# AugmentedStethoscope_v2b.net
KiCad netlist of a schematic drawn in EAGLE
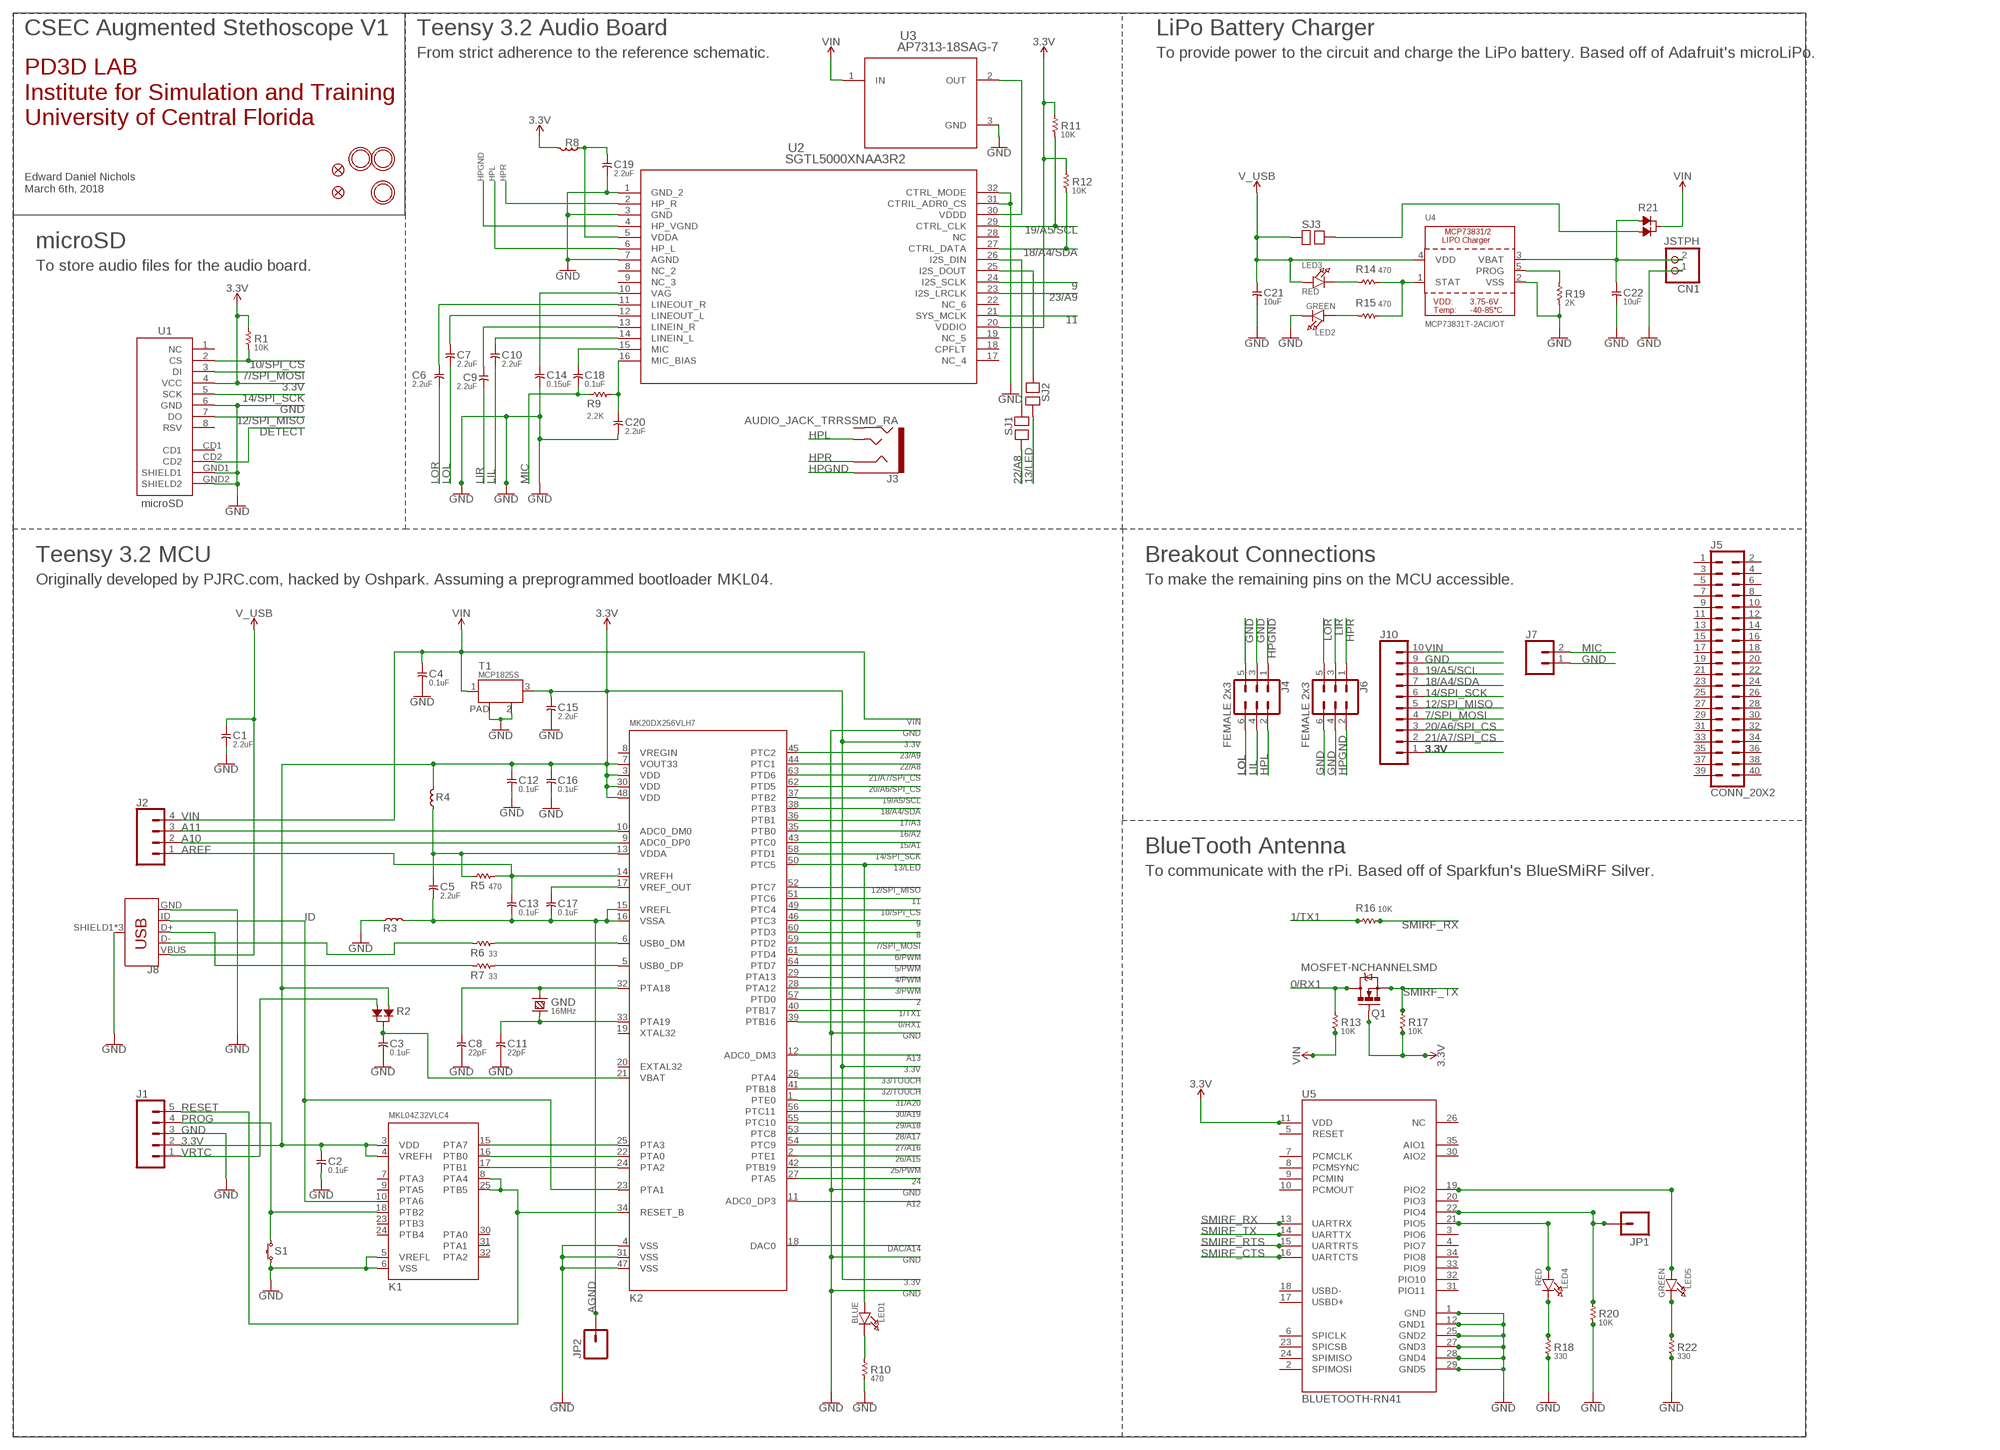
[diagram p0: schematic, sheet 1]

(export (version "E")
  (design (tool "Eeschema 10.0.6"))
  (components
    (comp (ref "C1")
      (value "2.2uF")
      (footprint "eagle-import:C0805")
      (fields (field (name "MF") "Taiyo Yuden") (field (name "MPN") "TMK212B7225KG-TR"))
      (libsource (lib "eagle-import") (part "CAPACITOR-2.2UF"))
    )
    (comp (ref "C2")
      (value "0.1uF")
      (footprint "eagle-import:C0603")
      (fields (field (name "MF") "Murata Electronics") (field (name "MPN") "GRM188R71C104KA01D"))
      (libsource (lib "eagle-import") (part "CAPACITOR-0.1UF"))
    )
    (comp (ref "C3")
      (value "0.1uF")
      (footprint "eagle-import:C0603")
      (fields (field (name "MF") "Murata Electronics") (field (name "MPN") "GRM188R71C104KA01D"))
      (libsource (lib "eagle-import") (part "CAPACITOR-0.1UF"))
    )
    (comp (ref "C4")
      (value "0.1uF")
      (footprint "eagle-import:C0603")
      (fields (field (name "MF") "Murata Electronics") (field (name "MPN") "GRM188R71C104KA01D"))
      (libsource (lib "eagle-import") (part "CAPACITOR-0.1UF"))
    )
    (comp (ref "C5")
      (value "2.2uF")
      (footprint "eagle-import:C0805")
      (fields (field (name "MF") "Taiyo Yuden") (field (name "MPN") "TMK212B7225KG-TR"))
      (libsource (lib "eagle-import") (part "CAPACITOR-2.2UF"))
    )
    (comp (ref "C6")
      (value "2.2uF")
      (footprint "eagle-import:C0805")
      (fields (field (name "MF") "Taiyo Yuden") (field (name "MPN") "TMK212B7225KG-TR"))
      (libsource (lib "eagle-import") (part "CAPACITOR-2.2UF"))
    )
    (comp (ref "C7")
      (value "2.2uF")
      (footprint "eagle-import:C0805")
      (fields (field (name "MF") "Taiyo Yuden") (field (name "MPN") "TMK212B7225KG-TR"))
      (libsource (lib "eagle-import") (part "CAPACITOR-2.2UF"))
    )
    (comp (ref "C8")
      (value "22pF")
      (footprint "eagle-import:C0603")
      (fields (field (name "MF") "Vishay / Vitramon") (field (name "MPN") "VJ0603A220JXACW1BC"))
      (libsource (lib "eagle-import") (part "CAPACITOR-22PF"))
    )
    (comp (ref "C9")
      (value "2.2uF")
      (footprint "eagle-import:C0805")
      (fields (field (name "MF") "Taiyo Yuden") (field (name "MPN") "TMK212B7225KG-TR"))
      (libsource (lib "eagle-import") (part "CAPACITOR-2.2UF"))
    )
    (comp (ref "C10")
      (value "2.2uF")
      (footprint "eagle-import:C0805")
      (fields (field (name "MF") "Taiyo Yuden") (field (name "MPN") "TMK212B7225KG-TR"))
      (libsource (lib "eagle-import") (part "CAPACITOR-2.2UF"))
    )
    (comp (ref "C11")
      (value "22pF")
      (footprint "eagle-import:C0603")
      (fields (field (name "MF") "Vishay / Vitramon") (field (name "MPN") "VJ0603A220JXACW1BC"))
      (libsource (lib "eagle-import") (part "CAPACITOR-22PF"))
    )
    (comp (ref "C12")
      (value "0.1uF")
      (footprint "eagle-import:C0603")
      (fields (field (name "MF") "Murata Electronics") (field (name "MPN") "GRM188R71C104KA01D"))
      (libsource (lib "eagle-import") (part "CAPACITOR-0.1UF"))
    )
    (comp (ref "C13")
      (value "0.1uF")
      (footprint "eagle-import:C0603")
      (fields (field (name "MF") "Murata Electronics") (field (name "MPN") "GRM188R71C104KA01D"))
      (libsource (lib "eagle-import") (part "CAPACITOR-0.1UF"))
    )
    (comp (ref "C14")
      (value "0.15uF")
      (footprint "eagle-import:C0805")
      (fields (field (name "MF") "Taiyo Yuden") (field (name "MPN") "TMK212B7225KG-TR"))
      (libsource (lib "eagle-import") (part "CAPACITOR-2.2UF"))
    )
    (comp (ref "C15")
      (value "2.2uF")
      (footprint "eagle-import:C0805")
      (fields (field (name "MF") "Taiyo Yuden") (field (name "MPN") "TMK212B7225KG-TR"))
      (libsource (lib "eagle-import") (part "CAPACITOR-2.2UF"))
    )
    (comp (ref "C16")
      (value "0.1uF")
      (footprint "eagle-import:C0603")
      (fields (field (name "MF") "Murata Electronics") (field (name "MPN") "GRM188R71C104KA01D"))
      (libsource (lib "eagle-import") (part "CAPACITOR-0.1UF"))
    )
    (comp (ref "C17")
      (value "0.1uF")
      (footprint "eagle-import:C0603")
      (fields (field (name "MF") "Murata Electronics") (field (name "MPN") "GRM188R71C104KA01D"))
      (libsource (lib "eagle-import") (part "CAPACITOR-0.1UF"))
    )
    (comp (ref "C18")
      (value "0.1uF")
      (footprint "eagle-import:C0805")
      (fields (field (name "MF") "Taiyo Yuden") (field (name "MPN") "TMK212B7225KG-TR"))
      (libsource (lib "eagle-import") (part "CAPACITOR-2.2UF"))
    )
    (comp (ref "C19")
      (value "2.2uF")
      (footprint "eagle-import:C0805")
      (fields (field (name "MF") "Taiyo Yuden") (field (name "MPN") "TMK212B7225KG-TR"))
      (libsource (lib "eagle-import") (part "CAPACITOR-2.2UF"))
    )
    (comp (ref "C20")
      (value "2.2uF")
      (footprint "eagle-import:C0805")
      (fields (field (name "MF") "Taiyo Yuden") (field (name "MPN") "TMK212B7225KG-TR"))
      (libsource (lib "eagle-import") (part "CAPACITOR-2.2UF"))
    )
    (comp (ref "C21")
      (value "10uF")
      (footprint "eagle-import:C0603")
      (fields (field (name "MF") "Murata Electronics") (field (name "MPN") "GRM188R71C104KA01D"))
      (libsource (lib "eagle-import") (part "CAPACITOR-0.1UF"))
    )
    (comp (ref "C22")
      (value "10uF")
      (footprint "eagle-import:C0603")
      (fields (field (name "MF") "Murata Electronics") (field (name "MPN") "GRM188R71C104KA01D"))
      (libsource (lib "eagle-import") (part "CAPACITOR-0.1UF"))
    )
    (comp (ref "CN1")
      (value "JSTPH")
      (footprint "eagle-import:JSTPH2")
      (libsource (lib "eagle-import") (part "JST_2PIN"))
    )
    (comp (ref "FID2")
      (value "FIDUCIAL\"\"")
      (footprint "eagle-import:FIDUCIAL_1MM")
      (libsource (lib "eagle-import") (part "FIDUCIAL{dblquote}{dblquote}"))
    )
    (comp (ref "FID3")
      (value "FIDUCIAL\"\"")
      (footprint "eagle-import:FIDUCIAL_1MM")
      (fields (field (name "BOM") "EXCLUDE"))
      (libsource (lib "eagle-import") (part "FIDUCIAL{dblquote}{dblquote}"))
    )
    (comp (ref "GND")
      (value "16MHz")
      (footprint "eagle-import:HC49US")
      (fields (field (name "MF") "ABRACON") (field (name "MPN") "ABL-16.000MHz-B1U"))
      (libsource (lib "eagle-import") (part "CRYSTAL-HC49US"))
    )
    (comp (ref "J1")
      (value "CONN_05")
      (footprint "eagle-import:1X05")
      (libsource (lib "eagle-import") (part "CONN_05"))
    )
    (comp (ref "J2")
      (value "CONN_04")
      (footprint "eagle-import:1X04")
      (libsource (lib "eagle-import") (part "CONN_04"))
    )
    (comp (ref "J3")
      (value "AUDIO_JACK_TRRSSMD_RA")
      (footprint "eagle-import:AUDIO_JACK_3.5MM_TRRS_SMD_RA")
      (libsource (lib "eagle-import") (part "AUDIO_JACK_TRRSSMD_RA"))
    )
    (comp (ref "J4")
      (value "FEMALE 2x3")
      (footprint "eagle-import:2X3")
      (libsource (lib "eagle-import") (part "CONN_03X2FEMALE"))
    )
    (comp (ref "J5")
      (value "CONN_20X2")
      (footprint "eagle-import:2X20")
      (libsource (lib "eagle-import") (part "CONN_20X2"))
    )
    (comp (ref "J6")
      (value "FEMALE 2x3")
      (footprint "eagle-import:2X3")
      (libsource (lib "eagle-import") (part "CONN_03X2FEMALE"))
    )
    (comp (ref "J7")
      (value "CONN_02")
      (footprint "eagle-import:1X02")
      (libsource (lib "eagle-import") (part "CONN_02"))
    )
    (comp (ref "J8")
      (value "USB_MICRO-B_FEMALE-SMT")
      (footprint "eagle-import:USB-B-MICRO-SMD")
      (libsource (lib "eagle-import") (part "USB_MICRO-B_FEMALE-SMT"))
    )
    (comp (ref "J10")
      (value "CONN_10\"")
      (footprint "eagle-import:1X10")
      (libsource (lib "eagle-import") (part "CONN_10{dblquote}"))
    )
    (comp (ref "JP1")
      (value "M01SMDNS")
      (footprint "eagle-import:1X01NS")
      (libsource (lib "eagle-import") (part "M01SMDNS"))
    )
    (comp (ref "JP2")
      (value "M01SMDNS")
      (footprint "eagle-import:1X01NS")
      (libsource (lib "eagle-import") (part "M01SMDNS"))
    )
    (comp (ref "K1")
      (value "MKL04Z32VLC4")
      (footprint "eagle-import:LQFP32-08")
      (fields (field (name "MF") "PJRC") (field (name "MPN") "IC_MKL04Z32_TQFP32"))
      (libsource (lib "eagle-import") (part "MKL04Z32VLC4"))
    )
    (comp (ref "K2")
      (value "MK20DX256VLH7")
      (footprint "eagle-import:LQFP64-05")
      (fields (field (name "MF") "NXP"))
      (libsource (lib "eagle-import") (part "MK20DX256VLH7"))
    )
    (comp (ref "LED1")
      (value "BLUE")
      (footprint "eagle-import:CHIPLED_0805")
      (libsource (lib "eagle-import") (part "LED0805"))
    )
    (comp (ref "LED2")
      (value "GREEN")
      (footprint "eagle-import:CHIPLED_0805")
      (libsource (lib "eagle-import") (part "LED0805"))
    )
    (comp (ref "LED3")
      (value "RED")
      (footprint "eagle-import:CHIPLED_0805")
      (libsource (lib "eagle-import") (part "LED0805"))
    )
    (comp (ref "LED4")
      (value "RED")
      (footprint "eagle-import:CHIPLED_0805")
      (libsource (lib "eagle-import") (part "LED0805"))
    )
    (comp (ref "LED5")
      (value "GREEN")
      (footprint "eagle-import:CHIPLED_0805")
      (libsource (lib "eagle-import") (part "LED0805"))
    )
    (comp (ref "Q1")
      (value "MOSFET-NCHANNELSMD")
      (footprint "eagle-import:SOT23-3")
      (libsource (lib "eagle-import") (part "MOSFET-NCHANNELSMD"))
    )
    (comp (ref "R1")
      (value "10K")
      (footprint "eagle-import:R0603")
      (fields (field (name "MF") "Vishay") (field (name "MPN") "CRCW0603470RFKEA"))
      (libsource (lib "eagle-import") (part "RESISTOR-470R"))
    )
    (comp (ref "R2")
      (value "DIODE_DUAL")
      (footprint "eagle-import:SOT-23")
      (fields (field (name "MF") "NXP Semiconductors") (field (name "MPN") "BAT54C,215"))
      (libsource (lib "eagle-import") (part "DIODE_DUAL"))
    )
    (comp (ref "R3")
      (value "FERRITE")
      (footprint "eagle-import:L0603")
      (fields (field (name "MF") "Murata Electronics") (field (name "MPN") " BLM18AG601SN1D"))
      (libsource (lib "eagle-import") (part "FERRITE"))
    )
    (comp (ref "R4")
      (value "FERRITE")
      (footprint "eagle-import:L0603")
      (fields (field (name "MF") "Murata Electronics") (field (name "MPN") " BLM18AG601SN1D"))
      (libsource (lib "eagle-import") (part "FERRITE"))
    )
    (comp (ref "R5")
      (value "470")
      (footprint "eagle-import:R0603")
      (fields (field (name "MF") "Vishay") (field (name "MPN") "CRCW0603470RFKEA"))
      (libsource (lib "eagle-import") (part "RESISTOR-470R"))
    )
    (comp (ref "R6")
      (value "33")
      (footprint "eagle-import:R0603")
      (fields (field (name "MF") "Panasonic") (field (name "MPN") "ERJ-PA3F33R0V"))
      (libsource (lib "eagle-import") (part "RESISTOR-33R"))
    )
    (comp (ref "R7")
      (value "33")
      (footprint "eagle-import:R0603")
      (fields (field (name "MF") "Panasonic") (field (name "MPN") "ERJ-PA3F33R0V"))
      (libsource (lib "eagle-import") (part "RESISTOR-33R"))
    )
    (comp (ref "R8")
      (value "FERRITE")
      (footprint "eagle-import:L0603")
      (fields (field (name "MF") "Murata Electronics") (field (name "MPN") " BLM18AG601SN1D"))
      (libsource (lib "eagle-import") (part "FERRITE"))
    )
    (comp (ref "R9")
      (value "2.2K")
      (footprint "eagle-import:R0603")
      (fields (field (name "MF") "Vishay") (field (name "MPN") "CRCW0603470RFKEA"))
      (libsource (lib "eagle-import") (part "RESISTOR-470R"))
    )
    (comp (ref "R10")
      (value "470")
      (footprint "eagle-import:R0603")
      (fields (field (name "MF") "Vishay") (field (name "MPN") "CRCW0603470RFKEA"))
      (libsource (lib "eagle-import") (part "RESISTOR-470R"))
    )
    (comp (ref "R11")
      (value "10K")
      (footprint "eagle-import:R0603")
      (fields (field (name "MF") "Vishay") (field (name "MPN") "CRCW0603470RFKEA"))
      (libsource (lib "eagle-import") (part "RESISTOR-470R"))
    )
    (comp (ref "R12")
      (value "10K")
      (footprint "eagle-import:R0603")
      (fields (field (name "MF") "Vishay") (field (name "MPN") "CRCW0603470RFKEA"))
      (libsource (lib "eagle-import") (part "RESISTOR-470R"))
    )
    (comp (ref "R13")
      (value "10K")
      (footprint "eagle-import:R0603")
      (fields (field (name "MF") "Vishay") (field (name "MPN") "CRCW0603470RFKEA"))
      (libsource (lib "eagle-import") (part "RESISTOR-470R"))
    )
    (comp (ref "R14")
      (value "470")
      (footprint "eagle-import:R0603")
      (fields (field (name "MF") "Panasonic") (field (name "MPN") "ERJ-PA3F33R0V"))
      (libsource (lib "eagle-import") (part "RESISTOR-33R"))
    )
    (comp (ref "R15")
      (value "470")
      (footprint "eagle-import:R0603")
      (fields (field (name "MF") "Panasonic") (field (name "MPN") "ERJ-PA3F33R0V"))
      (libsource (lib "eagle-import") (part "RESISTOR-33R"))
    )
    (comp (ref "R16")
      (value "10K")
      (footprint "eagle-import:R0603")
      (fields (field (name "MF") "Panasonic") (field (name "MPN") "ERJ-PA3F33R0V"))
      (libsource (lib "eagle-import") (part "RESISTOR-33R"))
    )
    (comp (ref "R17")
      (value "10K")
      (footprint "eagle-import:R0603")
      (fields (field (name "MF") "Vishay") (field (name "MPN") "CRCW0603470RFKEA"))
      (libsource (lib "eagle-import") (part "RESISTOR-470R"))
    )
    (comp (ref "R18")
      (value "330")
      (footprint "eagle-import:R0603")
      (fields (field (name "MF") "Vishay") (field (name "MPN") "CRCW0603470RFKEA"))
      (libsource (lib "eagle-import") (part "RESISTOR-470R"))
    )
    (comp (ref "R19")
      (value "2K")
      (footprint "eagle-import:R0603")
      (fields (field (name "MF") "Vishay") (field (name "MPN") "CRCW0603470RFKEA"))
      (libsource (lib "eagle-import") (part "RESISTOR-470R"))
    )
    (comp (ref "R20")
      (value "10K")
      (footprint "eagle-import:R0603")
      (fields (field (name "MF") "Vishay") (field (name "MPN") "CRCW0603470RFKEA"))
      (libsource (lib "eagle-import") (part "RESISTOR-470R"))
    )
    (comp (ref "R21")
      (value "DIODE_DUAL")
      (footprint "eagle-import:SOT-23")
      (fields (field (name "MF") "NXP Semiconductors") (field (name "MPN") "BAT54C,215"))
      (libsource (lib "eagle-import") (part "DIODE_DUAL"))
    )
    (comp (ref "R22")
      (value "330")
      (footprint "eagle-import:R0603")
      (fields (field (name "MF") "Vishay") (field (name "MPN") "CRCW0603470RFKEA"))
      (libsource (lib "eagle-import") (part "RESISTOR-470R"))
    )
    (comp (ref "S1")
      (value "TACT_SWITCH")
      (footprint "eagle-import:ALPS_SKHH")
      (fields (field (name "MF") "ALPS") (field (name "MPN") "SKHHPKA010"))
      (libsource (lib "eagle-import") (part "TACT_SWITCH"))
    )
    (comp (ref "SJ1")
      (value "SOLDERJUMPER")
      (footprint "eagle-import:SOLDERJUMPER")
      (libsource (lib "eagle-import") (part "SOLDERJUMPER"))
    )
    (comp (ref "SJ2")
      (value "SOLDERJUMPER")
      (footprint "eagle-import:SOLDERJUMPER")
      (libsource (lib "eagle-import") (part "SOLDERJUMPER"))
    )
    (comp (ref "SJ3")
      (value "SOLDERJUMPER")
      (footprint "eagle-import:SOLDERJUMPER")
      (libsource (lib "eagle-import") (part "SOLDERJUMPER"))
    )
    (comp (ref "T1")
      (value "MCP1825S")
      (footprint "eagle-import:SOT-223")
      (fields (field (name "MF") "Microchip Technology") (field (name "MPN") "MCP1825S-3302E/DB"))
      (libsource (lib "eagle-import") (part "LDO"))
    )
    (comp (ref "U$1")
      (value "MOUNTINGHOLE2.5")
      (footprint "eagle-import:MOUNTINGHOLE_2.5_PLATED")
      (libsource (lib "eagle-import") (part "MOUNTINGHOLE2.5"))
    )
    (comp (ref "U$15")
      (value "MOUNTINGHOLE2.5")
      (footprint "eagle-import:MOUNTINGHOLE_2.5_PLATED")
      (libsource (lib "eagle-import") (part "MOUNTINGHOLE2.5"))
    )
    (comp (ref "U$18")
      (value "MOUNTINGHOLE2.5")
      (footprint "eagle-import:MOUNTINGHOLE_2.5_PLATED")
      (libsource (lib "eagle-import") (part "MOUNTINGHOLE2.5"))
    )
    (comp (ref "U1")
      (value "microSD")
      (footprint "eagle-import:MICRO-SD-SOCKET-PP")
      (libsource (lib "eagle-import") (part "USD-SOCKETSMD"))
    )
    (comp (ref "U2")
      (value "SGTL5000XNAA3R2")
      (footprint "eagle-import:QFN32")
      (libsource (lib "eagle-import") (part "SGTL5000XNAA3R2"))
    )
    (comp (ref "U3")
      (value "AP7313-18SAG-7")
      (footprint "eagle-import:SOT-23")
      (fields (field (name "MANUFACTURER_PART_NUMBER") "AP731318SAG7"))
      (libsource (lib "eagle-import") (part "AP7313-18SAG-7"))
    )
    (comp (ref "U4")
      (value "MCP73831T-2ACI/OT")
      (footprint "eagle-import:SOT23-5")
      (libsource (lib "eagle-import") (part "MCP73831/2"))
    )
    (comp (ref "U5")
      (value "BLUETOOTH-RN41")
      (footprint "eagle-import:RN41")
      (libsource (lib "eagle-import") (part "BLUETOOTH-RN41{dblquote}"))
    )
  )
  (nets
    (net (code "1") (name "/0{slash}RX1") (class "Default")
      (node (ref "K2") (pin "39") (pinfunction "PTB16_39") (pintype "bidirectional"))
      (node (ref "Q1") (pin "3") (pinfunction "D_3") (pintype "passive"))
      (node (ref "R13") (pin "2") (pinfunction "2_2") (pintype "passive"))
    )
    (net (code "2") (name "/1{slash}TX1") (class "Default")
      (node (ref "K2") (pin "40") (pinfunction "PTB17_40") (pintype "bidirectional"))
      (node (ref "R16") (pin "1") (pinfunction "1_1") (pintype "passive"))
    )
    (net (code "3") (name "/2") (class "Default")
      (node (ref "K2") (pin "57") (pinfunction "PTD0_57") (pintype "bidirectional"))
    )
    (net (code "4") (name "/3{slash}PWM") (class "Default")
      (node (ref "K2") (pin "28") (pinfunction "PTA12_28") (pintype "bidirectional"))
    )
    (net (code "5") (name "/4{slash}PWM") (class "Default")
      (node (ref "K2") (pin "29") (pinfunction "PTA13_29") (pintype "bidirectional"))
    )
    (net (code "6") (name "/5{slash}PWM") (class "Default")
      (node (ref "K2") (pin "64") (pinfunction "PTD7_64") (pintype "bidirectional"))
    )
    (net (code "7") (name "/6{slash}PWM") (class "Default")
      (node (ref "K2") (pin "61") (pinfunction "PTD4_61") (pintype "bidirectional"))
    )
    (net (code "8") (name "/7{slash}SPI_MOSI") (class "Default")
      (node (ref "J10") (pin "4") (pinfunction "4_4") (pintype "passive"))
      (node (ref "K2") (pin "59") (pinfunction "PTD2_59") (pintype "bidirectional"))
      (node (ref "U1") (pin "3") (pinfunction "DI_3") (pintype "bidirectional"))
    )
    (net (code "9") (name "/8") (class "Default")
      (node (ref "K2") (pin "60") (pinfunction "PTD3_60") (pintype "bidirectional"))
    )
    (net (code "10") (name "/9") (class "Default")
      (node (ref "K2") (pin "46") (pinfunction "PTC3_46") (pintype "bidirectional"))
      (node (ref "U2") (pin "24") (pinfunction "I2S_SCLK_24") (pintype "passive"))
    )
    (net (code "11") (name "/10{slash}SPI_CS") (class "Default")
      (node (ref "K2") (pin "49") (pinfunction "PTC4_49") (pintype "bidirectional"))
      (node (ref "R1") (pin "1") (pinfunction "1_1") (pintype "passive"))
      (node (ref "U1") (pin "2") (pinfunction "CS_2") (pintype "bidirectional"))
    )
    (net (code "12") (name "/11") (class "Default")
      (node (ref "K2") (pin "51") (pinfunction "PTC6_51") (pintype "bidirectional"))
      (node (ref "U2") (pin "21") (pinfunction "SYS_MCLK_21") (pintype "passive"))
    )
    (net (code "13") (name "/12{slash}SPI_MISO") (class "Default")
      (node (ref "J10") (pin "5") (pinfunction "5_5") (pintype "passive"))
      (node (ref "K2") (pin "52") (pinfunction "PTC7_52") (pintype "bidirectional"))
      (node (ref "U1") (pin "7") (pinfunction "DO_7") (pintype "bidirectional"))
    )
    (net (code "14") (name "/13{slash}LED") (class "Default")
      (node (ref "K2") (pin "50") (pinfunction "PTC5_50") (pintype "bidirectional"))
      (node (ref "LED1") (pin "A") (pinfunction "A_A") (pintype "passive"))
      (node (ref "SJ2") (pin "2") (pinfunction "2_2") (pintype "passive"))
    )
    (net (code "15") (name "/14{slash}SPI_SCK") (class "Default")
      (node (ref "J10") (pin "6") (pinfunction "6_6") (pintype "passive"))
      (node (ref "K2") (pin "58") (pinfunction "PTD1_58") (pintype "bidirectional"))
      (node (ref "U1") (pin "5") (pinfunction "SCK_5") (pintype "bidirectional"))
    )
    (net (code "16") (name "/15{slash}A1") (class "Default")
      (node (ref "K2") (pin "43") (pinfunction "PTC0_43") (pintype "bidirectional"))
    )
    (net (code "17") (name "/16{slash}A2") (class "Default")
      (node (ref "K2") (pin "35") (pinfunction "PTB0_35") (pintype "bidirectional"))
    )
    (net (code "18") (name "/17{slash}A3") (class "Default")
      (node (ref "K2") (pin "36") (pinfunction "PTB1_36") (pintype "bidirectional"))
    )
    (net (code "19") (name "/18{slash}A4{slash}SDA") (class "Default")
      (node (ref "J10") (pin "7") (pinfunction "7_7") (pintype "passive"))
      (node (ref "K2") (pin "38") (pinfunction "PTB3_38") (pintype "bidirectional"))
      (node (ref "R12") (pin "1") (pinfunction "1_1") (pintype "passive"))
      (node (ref "U2") (pin "27") (pinfunction "CTRL_DATA_27") (pintype "passive"))
    )
    (net (code "20") (name "/19{slash}A5{slash}SCL") (class "Default")
      (node (ref "J10") (pin "8") (pinfunction "8_8") (pintype "passive"))
      (node (ref "K2") (pin "37") (pinfunction "PTB2_37") (pintype "bidirectional"))
      (node (ref "R11") (pin "1") (pinfunction "1_1") (pintype "passive"))
      (node (ref "U2") (pin "29") (pinfunction "CTRL_CLK_29") (pintype "passive"))
    )
    (net (code "21") (name "/20{slash}A6{slash}SPI_CS") (class "Default")
      (node (ref "J10") (pin "3") (pinfunction "3_3") (pintype "passive"))
      (node (ref "K2") (pin "62") (pinfunction "PTD5_62") (pintype "bidirectional"))
    )
    (net (code "22") (name "/21{slash}A7{slash}SPI_CS") (class "Default")
      (node (ref "J10") (pin "2") (pinfunction "2_2") (pintype "passive"))
      (node (ref "K2") (pin "63") (pinfunction "PTD6_63") (pintype "bidirectional"))
    )
    (net (code "23") (name "/22{slash}A8") (class "Default")
      (node (ref "K2") (pin "44") (pinfunction "PTC1_44") (pintype "bidirectional"))
      (node (ref "SJ1") (pin "2") (pinfunction "2_2") (pintype "passive"))
    )
    (net (code "24") (name "/23{slash}A9") (class "Default")
      (node (ref "K2") (pin "45") (pinfunction "PTC2_45") (pintype "bidirectional"))
      (node (ref "U2") (pin "23") (pinfunction "I2S_LRCLK_23") (pintype "passive"))
    )
    (net (code "25") (name "/24") (class "Default")
      (node (ref "K2") (pin "27") (pinfunction "PTA5_27") (pintype "bidirectional"))
    )
    (net (code "26") (name "/25{slash}PWM") (class "Default")
      (node (ref "K2") (pin "42") (pinfunction "PTB19_42") (pintype "bidirectional"))
    )
    (net (code "27") (name "/26{slash}A15") (class "Default")
      (node (ref "K2") (pin "2") (pinfunction "PTE1_2") (pintype "bidirectional"))
    )
    (net (code "28") (name "/27{slash}A16") (class "Default")
      (node (ref "K2") (pin "54") (pinfunction "PTC9_54") (pintype "bidirectional"))
    )
    (net (code "29") (name "/28{slash}A17") (class "Default")
      (node (ref "K2") (pin "53") (pinfunction "PTC8_53") (pintype "bidirectional"))
    )
    (net (code "30") (name "/29{slash}A18") (class "Default")
      (node (ref "K2") (pin "55") (pinfunction "PTC10_55") (pintype "bidirectional"))
    )
    (net (code "31") (name "/30{slash}A19") (class "Default")
      (node (ref "K2") (pin "56") (pinfunction "PTC11_56") (pintype "bidirectional"))
    )
    (net (code "32") (name "/31{slash}A20") (class "Default")
      (node (ref "K2") (pin "1") (pinfunction "PTE0_1") (pintype "bidirectional"))
    )
    (net (code "33") (name "/32{slash}TOUCH") (class "Default")
      (node (ref "K2") (pin "41") (pinfunction "PTB18_41") (pintype "bidirectional"))
    )
    (net (code "34") (name "/33{slash}TOUCH") (class "Default")
      (node (ref "K2") (pin "26") (pinfunction "PTA4_26") (pintype "bidirectional"))
    )
    (net (code "35") (name "/A10") (class "Default")
      (node (ref "J2") (pin "2") (pinfunction "2_2") (pintype "passive"))
      (node (ref "K2") (pin "9") (pinfunction "ADC0_DP0_9") (pintype "bidirectional"))
    )
    (net (code "36") (name "/A11") (class "Default")
      (node (ref "J2") (pin "3") (pinfunction "3_3") (pintype "passive"))
      (node (ref "K2") (pin "10") (pinfunction "ADC0_DM0_10") (pintype "bidirectional"))
    )
    (net (code "37") (name "/A12") (class "Default")
      (node (ref "K2") (pin "11") (pinfunction "ADC0_DP3_11") (pintype "bidirectional"))
    )
    (net (code "38") (name "/A13") (class "Default")
      (node (ref "K2") (pin "12") (pinfunction "ADC0_DM3_12") (pintype "bidirectional"))
    )
    (net (code "39") (name "/AGND") (class "Default")
      (node (ref "C13") (pin "2") (pinfunction "2_2") (pintype "passive"))
      (node (ref "C17") (pin "2") (pinfunction "2_2") (pintype "passive"))
      (node (ref "C5") (pin "2") (pinfunction "2_2") (pintype "passive"))
      (node (ref "JP2") (pin "1") (pinfunction "1_1") (pintype "passive"))
      (node (ref "K2") (pin "15") (pinfunction "VREFL_15") (pintype "bidirectional"))
      (node (ref "K2") (pin "16") (pinfunction "VSSA_16") (pintype "bidirectional"))
      (node (ref "R3") (pin "2") (pinfunction "2_2") (pintype "passive"))
    )
    (net (code "40") (name "/AREF") (class "Default")
      (node (ref "C13") (pin "1") (pinfunction "1_1") (pintype "passive"))
      (node (ref "J2") (pin "1") (pinfunction "1_1") (pintype "passive"))
      (node (ref "K2") (pin "14") (pinfunction "VREFH_14") (pintype "bidirectional"))
      (node (ref "R5") (pin "2") (pinfunction "2_2") (pintype "passive"))
    )
    (net (code "41") (name "/DAC{slash}A14") (class "Default")
      (node (ref "K2") (pin "18") (pinfunction "DAC0_18") (pintype "bidirectional"))
    )
    (net (code "42") (name "/DETECT") (class "Default")
      (node (ref "U1") (pin "CD2") (pinfunction "CD2_CD2") (pintype "bidirectional"))
    )
    (net (code "43") (name "/HPGND") (class "Default")
      (node (ref "J3") (pin "EARTH") (pinfunction "EARTH_EARTH") (pintype "bidirectional"))
      (node (ref "J4") (pin "1") (pinfunction "1_1") (pintype "bidirectional"))
      (node (ref "J6") (pin "2") (pinfunction "2_2") (pintype "bidirectional"))
      (node (ref "U2") (pin "4") (pinfunction "HP_VGND_4") (pintype "power_in"))
    )
    (net (code "44") (name "/HPL") (class "Default")
      (node (ref "J3") (pin "TIP") (pinfunction "TIP_TIP") (pintype "bidirectional"))
      (node (ref "J4") (pin "2") (pinfunction "2_2") (pintype "bidirectional"))
      (node (ref "U2") (pin "6") (pinfunction "HP_L_6") (pintype "output"))
    )
    (net (code "45") (name "/HPR") (class "Default")
      (node (ref "J3") (pin "RING1") (pinfunction "RING1_RING1") (pintype "bidirectional"))
      (node (ref "J6") (pin "1") (pinfunction "1_1") (pintype "bidirectional"))
      (node (ref "U2") (pin "2") (pinfunction "HP_R_2") (pintype "output"))
    )
    (net (code "46") (name "/ID") (class "Default")
      (node (ref "J8") (pin "ID") (pinfunction "ID_ID") (pintype "bidirectional"))
      (node (ref "K1") (pin "10") (pinfunction "PTA6_10") (pintype "bidirectional"))
      (node (ref "K2") (pin "23") (pinfunction "PTA1_23") (pintype "bidirectional"))
    )
    (net (code "47") (name "/LIL") (class "Default")
      (node (ref "C10") (pin "2") (pinfunction "2_2") (pintype "passive"))
      (node (ref "J4") (pin "4") (pinfunction "4_4") (pintype "bidirectional"))
    )
    (net (code "48") (name "/LIR") (class "Default")
      (node (ref "C9") (pin "2") (pinfunction "2_2") (pintype "passive"))
      (node (ref "J6") (pin "3") (pinfunction "3_3") (pintype "bidirectional"))
    )
    (net (code "49") (name "/LOL") (class "Default")
      (node (ref "C7") (pin "2") (pinfunction "2_2") (pintype "passive"))
      (node (ref "J4") (pin "6") (pinfunction "6_6") (pintype "bidirectional"))
    )
    (net (code "50") (name "/LOR") (class "Default")
      (node (ref "C6") (pin "2") (pinfunction "2_2") (pintype "passive"))
      (node (ref "J6") (pin "5") (pinfunction "5_5") (pintype "bidirectional"))
    )
    (net (code "51") (name "/MIC") (class "Default")
      (node (ref "C18") (pin "2") (pinfunction "2_2") (pintype "passive"))
      (node (ref "J7") (pin "2") (pinfunction "2_2") (pintype "passive"))
      (node (ref "R9") (pin "1") (pinfunction "1_1") (pintype "passive"))
    )
    (net (code "52") (name "/PROG") (class "Default")
      (node (ref "J1") (pin "4") (pinfunction "4_4") (pintype "passive"))
      (node (ref "K1") (pin "18") (pinfunction "PTB2_18") (pintype "bidirectional"))
      (node (ref "S1") (pin "1") (pinfunction "1_1") (pintype "passive"))
      (node (ref "S1") (pin "2") (pinfunction "1_2") (pintype "passive"))
    )
    (net (code "53") (name "/RESET") (class "Default")
      (node (ref "J1") (pin "5") (pinfunction "5_5") (pintype "passive"))
      (node (ref "K1") (pin "25") (pinfunction "PTB5_25") (pintype "bidirectional"))
      (node (ref "K1") (pin "8") (pinfunction "PTA4_8") (pintype "bidirectional"))
      (node (ref "K2") (pin "34") (pinfunction "RESET_B_34") (pintype "bidirectional"))
    )
    (net (code "54") (name "/SMIRF_CTS") (class "Default")
      (node (ref "U5") (pin "16") (pinfunction "UARTCTS_16") (pintype "bidirectional"))
    )
    (net (code "55") (name "/SMIRF_RTS") (class "Default")
      (node (ref "U5") (pin "15") (pinfunction "UARTRTS_15") (pintype "bidirectional"))
    )
    (net (code "56") (name "/SMIRF_RX") (class "Default")
      (node (ref "R16") (pin "2") (pinfunction "2_2") (pintype "passive"))
      (node (ref "U5") (pin "13") (pinfunction "UARTRX_13") (pintype "bidirectional"))
    )
    (net (code "57") (name "/SMIRF_TX") (class "Default")
      (node (ref "Q1") (pin "2") (pinfunction "S_2") (pintype "passive"))
      (node (ref "R17") (pin "2") (pinfunction "2_2") (pintype "passive"))
      (node (ref "U5") (pin "14") (pinfunction "UARTTX_14") (pintype "bidirectional"))
    )
    (net (code "58") (name "/VRTC") (class "Default")
      (node (ref "J1") (pin "1") (pinfunction "1_1") (pintype "passive"))
      (node (ref "R2") (pin "2") (pinfunction "2_2") (pintype "bidirectional"))
    )
    (net (code "59") (name "3.3V") (class "Default")
      (node (ref "C12") (pin "1") (pinfunction "1_1") (pintype "passive"))
      (node (ref "C15") (pin "1") (pinfunction "1_1") (pintype "passive"))
      (node (ref "C16") (pin "1") (pinfunction "1_1") (pintype "passive"))
      (node (ref "C2") (pin "1") (pinfunction "1_1") (pintype "passive"))
      (node (ref "J1") (pin "2") (pinfunction "2_2") (pintype "passive"))
      (node (ref "J10") (pin "1") (pinfunction "1_1") (pintype "passive"))
      (node (ref "K1") (pin "3") (pinfunction "VDD_3") (pintype "bidirectional"))
      (node (ref "K1") (pin "4") (pinfunction "VREFH_4") (pintype "bidirectional"))
      (node (ref "K2") (pin "3") (pinfunction "VDD_3") (pintype "bidirectional"))
      (node (ref "K2") (pin "30") (pinfunction "VDD_30") (pintype "bidirectional"))
      (node (ref "K2") (pin "48") (pinfunction "VDD_48") (pintype "bidirectional"))
      (node (ref "K2") (pin "7") (pinfunction "VOUT33_7") (pintype "bidirectional"))
      (node (ref "Q1") (pin "1") (pinfunction "G_1") (pintype "passive"))
      (node (ref "R1") (pin "2") (pinfunction "2_2") (pintype "passive"))
      (node (ref "R11") (pin "2") (pinfunction "2_2") (pintype "passive"))
      (node (ref "R12") (pin "2") (pinfunction "2_2") (pintype "passive"))
      (node (ref "R17") (pin "1") (pinfunction "1_1") (pintype "passive"))
      (node (ref "R2") (pin "1") (pinfunction "1_1") (pintype "bidirectional"))
      (node (ref "R4") (pin "2") (pinfunction "2_2") (pintype "passive"))
      (node (ref "R8") (pin "2") (pinfunction "2_2") (pintype "passive"))
      (node (ref "T1") (pin "3") (pinfunction "OUT_3") (pintype "bidirectional"))
      (node (ref "U1") (pin "4") (pinfunction "VCC_4") (pintype "bidirectional"))
      (node (ref "U2") (pin "20") (pinfunction "VDDIO_20") (pintype "power_in"))
      (node (ref "U5") (pin "11") (pinfunction "VDD_11") (pintype "bidirectional"))
    )
    (net (code "60") (name "GND") (class "Default")
      (node (ref "C1") (pin "2") (pinfunction "2_2") (pintype "passive"))
      (node (ref "C11") (pin "2") (pinfunction "2_2") (pintype "passive"))
      (node (ref "C12") (pin "2") (pinfunction "2_2") (pintype "passive"))
      (node (ref "C14") (pin "2") (pinfunction "2_2") (pintype "passive"))
      (node (ref "C15") (pin "2") (pinfunction "2_2") (pintype "passive"))
      (node (ref "C16") (pin "2") (pinfunction "2_2") (pintype "passive"))
      (node (ref "C19") (pin "2") (pinfunction "2_2") (pintype "passive"))
      (node (ref "C2") (pin "2") (pinfunction "2_2") (pintype "passive"))
      (node (ref "C20") (pin "2") (pinfunction "2_2") (pintype "passive"))
      (node (ref "C21") (pin "2") (pinfunction "2_2") (pintype "passive"))
      (node (ref "C22") (pin "2") (pinfunction "2_2") (pintype "passive"))
      (node (ref "C3") (pin "2") (pinfunction "2_2") (pintype "passive"))
      (node (ref "C4") (pin "2") (pinfunction "2_2") (pintype "passive"))
      (node (ref "C8") (pin "2") (pinfunction "2_2") (pintype "passive"))
      (node (ref "CN1") (pin "1") (pinfunction "1_1") (pintype "passive"))
      (node (ref "J1") (pin "3") (pinfunction "3_3") (pintype "passive"))
      (node (ref "J10") (pin "9") (pinfunction "9_9") (pintype "passive"))
      (node (ref "J4") (pin "3") (pinfunction "3_3") (pintype "bidirectional"))
      (node (ref "J4") (pin "5") (pinfunction "5_5") (pintype "bidirectional"))
      (node (ref "J6") (pin "4") (pinfunction "4_4") (pintype "bidirectional"))
      (node (ref "J6") (pin "6") (pinfunction "6_6") (pintype "bidirectional"))
      (node (ref "J7") (pin "1") (pinfunction "1_1") (pintype "passive"))
      (node (ref "J8") (pin "GND") (pinfunction "GND_GND") (pintype "power_in"))
      (node (ref "J8") (pin "SHIELD1") (pinfunction "SHIELD_SHIELD1") (pintype "bidirectional"))
      (node (ref "J8") (pin "SHIELD2") (pinfunction "SHIELD_SHIELD2") (pintype "bidirectional"))
      (node (ref "J8") (pin "SHIELD3") (pinfunction "SHIELD_SHIELD3") (pintype "bidirectional"))
      (node (ref "K1") (pin "5") (pinfunction "VREFL_5") (pintype "bidirectional"))
      (node (ref "K1") (pin "6") (pinfunction "VSS_6") (pintype "bidirectional"))
      (node (ref "K2") (pin "31") (pinfunction "VSS_31") (pintype "bidirectional"))
      (node (ref "K2") (pin "4") (pinfunction "VSS_4") (pintype "bidirectional"))
      (node (ref "K2") (pin "47") (pinfunction "VSS_47") (pintype "bidirectional"))
      (node (ref "LED2") (pin "C") (pinfunction "C_C") (pintype "passive"))
      (node (ref "R10") (pin "1") (pinfunction "1_1") (pintype "passive"))
      (node (ref "R18") (pin "1") (pinfunction "1_1") (pintype "passive"))
      (node (ref "R19") (pin "1") (pinfunction "1_1") (pintype "passive"))
      (node (ref "R20") (pin "1") (pinfunction "1_1") (pintype "passive"))
      (node (ref "R22") (pin "1") (pinfunction "1_1") (pintype "passive"))
      (node (ref "R3") (pin "1") (pinfunction "1_1") (pintype "passive"))
      (node (ref "S1") (pin "3") (pinfunction "3_3") (pintype "passive"))
      (node (ref "S1") (pin "4") (pinfunction "3_4") (pintype "passive"))
      (node (ref "T1") (pin "2") (pinfunction "GND_2") (pintype "bidirectional"))
      (node (ref "T1") (pin "PAD") (pinfunction "PAD_PAD") (pintype "bidirectional"))
      (node (ref "U1") (pin "6") (pinfunction "GND_6") (pintype "bidirectional"))
      (node (ref "U1") (pin "GND1") (pinfunction "SHIELD1_GND1") (pintype "bidirectional"))
      (node (ref "U1") (pin "GND2") (pinfunction "SHIELD2_GND2") (pintype "bidirectional"))
      (node (ref "U2") (pin "1") (pinfunction "GND_2_1") (pintype "power_in"))
      (node (ref "U2") (pin "3") (pinfunction "GND_3") (pintype "power_in"))
      (node (ref "U2") (pin "31") (pinfunction "CTRIL_ADR0_CS_31") (pintype "passive"))
      (node (ref "U2") (pin "32") (pinfunction "CTRL_MODE_32") (pintype "passive"))
      (node (ref "U2") (pin "7") (pinfunction "AGND_7") (pintype "power_in"))
      (node (ref "U3") (pin "3") (pinfunction "GND_3") (pintype "power_in"))
      (node (ref "U4") (pin "2") (pinfunction "VSS_2") (pintype "power_in"))
      (node (ref "U5") (pin "1") (pinfunction "GND_1") (pintype "bidirectional"))
      (node (ref "U5") (pin "12") (pinfunction "GND1_12") (pintype "bidirectional"))
      (node (ref "U5") (pin "25") (pinfunction "GND2_25") (pintype "bidirectional"))
      (node (ref "U5") (pin "27") (pinfunction "GND3_27") (pintype "bidirectional"))
      (node (ref "U5") (pin "28") (pinfunction "GND4_28") (pintype "bidirectional"))
      (node (ref "U5") (pin "29") (pinfunction "GND5_29") (pintype "bidirectional"))
    )
    (net (code "61") (name "Net-(J8-PadD+)") (class "Default")
      (node (ref "J8") (pin "D+") (pinfunction "D+_D+") (pintype "bidirectional"))
      (node (ref "R7") (pin "1") (pinfunction "1_1") (pintype "passive"))
    )
    (net (code "62") (name "Net-(J8-PadD-)") (class "Default")
      (node (ref "J8") (pin "D-") (pinfunction "D-_D-") (pintype "bidirectional"))
      (node (ref "R6") (pin "1") (pinfunction "1_1") (pintype "passive"))
    )
    (net (code "63") (name "Net-(K1-PTA7)") (class "Default")
      (node (ref "K1") (pin "15") (pinfunction "PTA7_15") (pintype "bidirectional"))
      (node (ref "K2") (pin "25") (pinfunction "PTA3_25") (pintype "bidirectional"))
    )
    (net (code "64") (name "Net-(K1-PTB0)") (class "Default")
      (node (ref "K1") (pin "16") (pinfunction "PTB0_16") (pintype "bidirectional"))
      (node (ref "K2") (pin "22") (pinfunction "PTA0_22") (pintype "bidirectional"))
    )
    (net (code "65") (name "Net-(K1-PTB1)") (class "Default")
      (node (ref "K1") (pin "17") (pinfunction "PTB1_17") (pintype "bidirectional"))
      (node (ref "K2") (pin "24") (pinfunction "PTA2_24") (pintype "bidirectional"))
    )
    (net (code "66") (name "Net-(K2-PTA18)") (class "Default")
      (node (ref "C8") (pin "1") (pinfunction "1_1") (pintype "passive"))
      (node (ref "GND") (pin "1") (pinfunction "1_1") (pintype "passive"))
      (node (ref "K2") (pin "32") (pinfunction "PTA18_32") (pintype "bidirectional"))
    )
    (net (code "67") (name "Net-(K2-PTA19)") (class "Default")
      (node (ref "C11") (pin "1") (pinfunction "1_1") (pintype "passive"))
      (node (ref "GND") (pin "2") (pinfunction "2_2") (pintype "passive"))
      (node (ref "K2") (pin "33") (pinfunction "PTA19_33") (pintype "bidirectional"))
    )
    (net (code "68") (name "Net-(K2-USB0_DM)") (class "Default")
      (node (ref "K2") (pin "6") (pinfunction "USB0_DM_6") (pintype "bidirectional"))
      (node (ref "R6") (pin "2") (pinfunction "2_2") (pintype "passive"))
    )
    (net (code "69") (name "Net-(K2-USB0_DP)") (class "Default")
      (node (ref "K2") (pin "5") (pinfunction "USB0_DP_5") (pintype "bidirectional"))
      (node (ref "R7") (pin "2") (pinfunction "2_2") (pintype "passive"))
    )
    (net (code "70") (name "Net-(K2-VBAT)") (class "Default")
      (node (ref "C3") (pin "1") (pinfunction "1_1") (pintype "passive"))
      (node (ref "K2") (pin "21") (pinfunction "VBAT_21") (pintype "bidirectional"))
      (node (ref "R2") (pin "3") (pinfunction "3_3") (pintype "bidirectional"))
    )
    (net (code "71") (name "Net-(K2-VDDA)") (class "Default")
      (node (ref "C5") (pin "1") (pinfunction "1_1") (pintype "passive"))
      (node (ref "K2") (pin "13") (pinfunction "VDDA_13") (pintype "bidirectional"))
      (node (ref "R4") (pin "1") (pinfunction "1_1") (pintype "passive"))
      (node (ref "R5") (pin "1") (pinfunction "1_1") (pintype "passive"))
    )
    (net (code "72") (name "Net-(K2-VREF_OUT)") (class "Default")
      (node (ref "C17") (pin "1") (pinfunction "1_1") (pintype "passive"))
      (node (ref "K2") (pin "17") (pinfunction "VREF_OUT_17") (pintype "bidirectional"))
    )
    (net (code "73") (name "Net-(LED1-PadC)") (class "Default")
      (node (ref "LED1") (pin "C") (pinfunction "C_C") (pintype "passive"))
      (node (ref "R10") (pin "2") (pinfunction "2_2") (pintype "passive"))
    )
    (net (code "74") (name "Net-(LED2-PadA)") (class "Default")
      (node (ref "LED2") (pin "A") (pinfunction "A_A") (pintype "passive"))
      (node (ref "R15") (pin "1") (pinfunction "1_1") (pintype "passive"))
    )
    (net (code "75") (name "Net-(LED3-PadC)") (class "Default")
      (node (ref "LED3") (pin "C") (pinfunction "C_C") (pintype "passive"))
      (node (ref "R14") (pin "1") (pinfunction "1_1") (pintype "passive"))
    )
    (net (code "76") (name "Net-(LED4-PadC)") (class "Default")
      (node (ref "LED4") (pin "C") (pinfunction "C_C") (pintype "passive"))
      (node (ref "R18") (pin "2") (pinfunction "2_2") (pintype "passive"))
    )
    (net (code "77") (name "Net-(LED5-PadC)") (class "Default")
      (node (ref "LED5") (pin "C") (pinfunction "C_C") (pintype "passive"))
      (node (ref "R22") (pin "2") (pinfunction "2_2") (pintype "passive"))
    )
    (net (code "78") (name "Net-(R21-Pad2)") (class "Default")
      (node (ref "R21") (pin "2") (pinfunction "2_2") (pintype "bidirectional"))
      (node (ref "SJ3") (pin "2") (pinfunction "2_2") (pintype "passive"))
    )
    (net (code "79") (name "Net-(U2-I2S_DIN)") (class "Default")
      (node (ref "SJ1") (pin "1") (pinfunction "1_1") (pintype "passive"))
      (node (ref "U2") (pin "26") (pinfunction "I2S_DIN_26") (pintype "input"))
    )
    (net (code "80") (name "Net-(U2-I2S_DOUT)") (class "Default")
      (node (ref "SJ2") (pin "1") (pinfunction "1_1") (pintype "passive"))
      (node (ref "U2") (pin "25") (pinfunction "I2S_DOUT_25") (pintype "output"))
    )
    (net (code "81") (name "Net-(U2-LINEIN_L)") (class "Default")
      (node (ref "C10") (pin "1") (pinfunction "1_1") (pintype "passive"))
      (node (ref "U2") (pin "14") (pinfunction "LINEIN_L_14") (pintype "input"))
    )
    (net (code "82") (name "Net-(U2-LINEIN_R)") (class "Default")
      (node (ref "C9") (pin "1") (pinfunction "1_1") (pintype "passive"))
      (node (ref "U2") (pin "13") (pinfunction "LINEIN_R_13") (pintype "input"))
    )
    (net (code "83") (name "Net-(U2-LINEOUT_L)") (class "Default")
      (node (ref "C7") (pin "1") (pinfunction "1_1") (pintype "passive"))
      (node (ref "U2") (pin "12") (pinfunction "LINEOUT_L_12") (pintype "output"))
    )
    (net (code "84") (name "Net-(U2-LINEOUT_R)") (class "Default")
      (node (ref "C6") (pin "1") (pinfunction "1_1") (pintype "passive"))
      (node (ref "U2") (pin "11") (pinfunction "LINEOUT_R_11") (pintype "output"))
    )
    (net (code "85") (name "Net-(U2-MIC)") (class "Default")
      (node (ref "C18") (pin "1") (pinfunction "1_1") (pintype "passive"))
      (node (ref "U2") (pin "15") (pinfunction "MIC_15") (pintype "input"))
    )
    (net (code "86") (name "Net-(U2-MIC_BIAS)") (class "Default")
      (node (ref "C20") (pin "1") (pinfunction "1_1") (pintype "passive"))
      (node (ref "R9") (pin "2") (pinfunction "2_2") (pintype "passive"))
      (node (ref "U2") (pin "16") (pinfunction "MIC_BIAS_16") (pintype "passive"))
    )
    (net (code "87") (name "Net-(U2-VAG)") (class "Default")
      (node (ref "C14") (pin "1") (pinfunction "1_1") (pintype "passive"))
      (node (ref "U2") (pin "10") (pinfunction "VAG_10") (pintype "passive"))
    )
    (net (code "88") (name "Net-(U2-VDDA)") (class "Default")
      (node (ref "C19") (pin "1") (pinfunction "1_1") (pintype "passive"))
      (node (ref "R8") (pin "1") (pinfunction "1_1") (pintype "passive"))
      (node (ref "U2") (pin "5") (pinfunction "VDDA_5") (pintype "power_in"))
    )
    (net (code "89") (name "Net-(U2-VDDD)") (class "Default")
      (node (ref "U2") (pin "30") (pinfunction "VDDD_30") (pintype "power_in"))
      (node (ref "U3") (pin "2") (pinfunction "OUT_2") (pintype "output"))
    )
    (net (code "90") (name "Net-(U4-PROG)") (class "Default")
      (node (ref "R19") (pin "2") (pinfunction "2_2") (pintype "passive"))
      (node (ref "U4") (pin "5") (pinfunction "PROG_5") (pintype "input"))
    )
    (net (code "91") (name "Net-(U4-STAT)") (class "Default")
      (node (ref "R14") (pin "2") (pinfunction "2_2") (pintype "passive"))
      (node (ref "R15") (pin "2") (pinfunction "2_2") (pintype "passive"))
      (node (ref "U4") (pin "1") (pinfunction "STAT_1") (pintype "output"))
    )
    (net (code "92") (name "Net-(U4-VBAT)") (class "Default")
      (node (ref "C22") (pin "1") (pinfunction "1_1") (pintype "passive"))
      (node (ref "CN1") (pin "2") (pinfunction "2_2") (pintype "passive"))
      (node (ref "R21") (pin "1") (pinfunction "1_1") (pintype "bidirectional"))
      (node (ref "U4") (pin "3") (pinfunction "VBAT_3") (pintype "power_in"))
    )
    (net (code "93") (name "Net-(U5-PIO2)") (class "Default")
      (node (ref "LED5") (pin "A") (pinfunction "A_A") (pintype "passive"))
      (node (ref "U5") (pin "19") (pinfunction "PIO2_19") (pintype "bidirectional"))
    )
    (net (code "94") (name "Net-(U5-PIO4)") (class "Default")
      (node (ref "JP1") (pin "1") (pinfunction "1_1") (pintype "passive"))
      (node (ref "R20") (pin "2") (pinfunction "2_2") (pintype "passive"))
      (node (ref "U5") (pin "22") (pinfunction "PIO4_22") (pintype "bidirectional"))
    )
    (net (code "95") (name "Net-(U5-PIO5)") (class "Default")
      (node (ref "LED4") (pin "A") (pinfunction "A_A") (pintype "passive"))
      (node (ref "U5") (pin "21") (pinfunction "PIO5_21") (pintype "bidirectional"))
    )
    (net (code "96") (name "VIN") (class "Default")
      (node (ref "C4") (pin "1") (pinfunction "1_1") (pintype "passive"))
      (node (ref "J10") (pin "10") (pinfunction "10_10") (pintype "passive"))
      (node (ref "J2") (pin "4") (pinfunction "4_4") (pintype "passive"))
      (node (ref "R13") (pin "1") (pinfunction "1_1") (pintype "passive"))
      (node (ref "R21") (pin "3") (pinfunction "3_3") (pintype "bidirectional"))
      (node (ref "T1") (pin "1") (pinfunction "IN_1") (pintype "bidirectional"))
      (node (ref "U3") (pin "1") (pinfunction "IN_1") (pintype "input"))
    )
    (net (code "97") (name "V_USB") (class "Default")
      (node (ref "C1") (pin "1") (pinfunction "1_1") (pintype "passive"))
      (node (ref "C21") (pin "1") (pinfunction "1_1") (pintype "passive"))
      (node (ref "J8") (pin "VBUS") (pinfunction "VBUS_VBUS") (pintype "power_in"))
      (node (ref "LED3") (pin "A") (pinfunction "A_A") (pintype "passive"))
      (node (ref "SJ3") (pin "1") (pinfunction "1_1") (pintype "passive"))
      (node (ref "U4") (pin "4") (pinfunction "VDD_4") (pintype "power_in"))
    )
    (net (code "98") (name "unconnected-(J3-PadRING2)") (class "Default")
      (node (ref "J3") (pin "RING2") (pinfunction "RING2_RING2") (pintype "bidirectional"))
    )
    (net (code "99") (name "unconnected-(J5-Pad1)") (class "Default")
      (node (ref "J5") (pin "1") (pinfunction "1_1") (pintype "passive"))
    )
    (net (code "100") (name "unconnected-(J5-Pad2)") (class "Default")
      (node (ref "J5") (pin "2") (pinfunction "2_2") (pintype "passive"))
    )
    (net (code "101") (name "unconnected-(J5-Pad3)") (class "Default")
      (node (ref "J5") (pin "3") (pinfunction "3_3") (pintype "passive"))
    )
    (net (code "102") (name "unconnected-(J5-Pad4)") (class "Default")
      (node (ref "J5") (pin "4") (pinfunction "4_4") (pintype "passive"))
    )
    (net (code "103") (name "unconnected-(J5-Pad5)") (class "Default")
      (node (ref "J5") (pin "5") (pinfunction "5_5") (pintype "passive"))
    )
    (net (code "104") (name "unconnected-(J5-Pad6)") (class "Default")
      (node (ref "J5") (pin "6") (pinfunction "6_6") (pintype "passive"))
    )
    (net (code "105") (name "unconnected-(J5-Pad7)") (class "Default")
      (node (ref "J5") (pin "7") (pinfunction "7_7") (pintype "passive"))
    )
    (net (code "106") (name "unconnected-(J5-Pad8)") (class "Default")
      (node (ref "J5") (pin "8") (pinfunction "8_8") (pintype "passive"))
    )
    (net (code "107") (name "unconnected-(J5-Pad9)") (class "Default")
      (node (ref "J5") (pin "9") (pinfunction "9_9") (pintype "passive"))
    )
    (net (code "108") (name "unconnected-(J5-Pad10)") (class "Default")
      (node (ref "J5") (pin "10") (pinfunction "10_10") (pintype "passive"))
    )
    (net (code "109") (name "unconnected-(J5-Pad11)") (class "Default")
      (node (ref "J5") (pin "11") (pinfunction "11_11") (pintype "passive"))
    )
    (net (code "110") (name "unconnected-(J5-Pad12)") (class "Default")
      (node (ref "J5") (pin "12") (pinfunction "12_12") (pintype "passive"))
    )
    (net (code "111") (name "unconnected-(J5-Pad13)") (class "Default")
      (node (ref "J5") (pin "13") (pinfunction "13_13") (pintype "passive"))
    )
    (net (code "112") (name "unconnected-(J5-Pad14)") (class "Default")
      (node (ref "J5") (pin "14") (pinfunction "14_14") (pintype "passive"))
    )
    (net (code "113") (name "unconnected-(J5-Pad15)") (class "Default")
      (node (ref "J5") (pin "15") (pinfunction "15_15") (pintype "passive"))
    )
    (net (code "114") (name "unconnected-(J5-Pad16)") (class "Default")
      (node (ref "J5") (pin "16") (pinfunction "16_16") (pintype "passive"))
    )
    (net (code "115") (name "unconnected-(J5-Pad17)") (class "Default")
      (node (ref "J5") (pin "17") (pinfunction "17_17") (pintype "passive"))
    )
    (net (code "116") (name "unconnected-(J5-Pad18)") (class "Default")
      (node (ref "J5") (pin "18") (pinfunction "18_18") (pintype "passive"))
    )
    (net (code "117") (name "unconnected-(J5-Pad19)") (class "Default")
      (node (ref "J5") (pin "19") (pinfunction "19_19") (pintype "passive"))
    )
    (net (code "118") (name "unconnected-(J5-Pad20)") (class "Default")
      (node (ref "J5") (pin "20") (pinfunction "20_20") (pintype "passive"))
    )
    (net (code "119") (name "unconnected-(J5-Pad21)") (class "Default")
      (node (ref "J5") (pin "21") (pinfunction "21_21") (pintype "passive"))
    )
    (net (code "120") (name "unconnected-(J5-Pad22)") (class "Default")
      (node (ref "J5") (pin "22") (pinfunction "22_22") (pintype "passive"))
    )
    (net (code "121") (name "unconnected-(J5-Pad23)") (class "Default")
      (node (ref "J5") (pin "23") (pinfunction "23_23") (pintype "passive"))
    )
    (net (code "122") (name "unconnected-(J5-Pad24)") (class "Default")
      (node (ref "J5") (pin "24") (pinfunction "24_24") (pintype "passive"))
    )
    (net (code "123") (name "unconnected-(J5-Pad25)") (class "Default")
      (node (ref "J5") (pin "25") (pinfunction "25_25") (pintype "passive"))
    )
    (net (code "124") (name "unconnected-(J5-Pad26)") (class "Default")
      (node (ref "J5") (pin "26") (pinfunction "26_26") (pintype "passive"))
    )
    (net (code "125") (name "unconnected-(J5-Pad27)") (class "Default")
      (node (ref "J5") (pin "27") (pinfunction "27_27") (pintype "passive"))
    )
    (net (code "126") (name "unconnected-(J5-Pad28)") (class "Default")
      (node (ref "J5") (pin "28") (pinfunction "28_28") (pintype "passive"))
    )
    (net (code "127") (name "unconnected-(J5-Pad29)") (class "Default")
      (node (ref "J5") (pin "29") (pinfunction "29_29") (pintype "passive"))
    )
    (net (code "128") (name "unconnected-(J5-Pad30)") (class "Default")
      (node (ref "J5") (pin "30") (pinfunction "30_30") (pintype "passive"))
    )
    (net (code "129") (name "unconnected-(J5-Pad31)") (class "Default")
      (node (ref "J5") (pin "31") (pinfunction "31_31") (pintype "passive"))
    )
    (net (code "130") (name "unconnected-(J5-Pad32)") (class "Default")
      (node (ref "J5") (pin "32") (pinfunction "32_32") (pintype "passive"))
    )
    (net (code "131") (name "unconnected-(J5-Pad33)") (class "Default")
      (node (ref "J5") (pin "33") (pinfunction "33_33") (pintype "passive"))
    )
    (net (code "132") (name "unconnected-(J5-Pad34)") (class "Default")
      (node (ref "J5") (pin "34") (pinfunction "34_34") (pintype "passive"))
    )
    (net (code "133") (name "unconnected-(J5-Pad35)") (class "Default")
      (node (ref "J5") (pin "35") (pinfunction "35_35") (pintype "passive"))
    )
    (net (code "134") (name "unconnected-(J5-Pad36)") (class "Default")
      (node (ref "J5") (pin "36") (pinfunction "36_36") (pintype "passive"))
    )
    (net (code "135") (name "unconnected-(J5-Pad37)") (class "Default")
      (node (ref "J5") (pin "37") (pinfunction "37_37") (pintype "passive"))
    )
    (net (code "136") (name "unconnected-(J5-Pad38)") (class "Default")
      (node (ref "J5") (pin "38") (pinfunction "38_38") (pintype "passive"))
    )
    (net (code "137") (name "unconnected-(J5-Pad39)") (class "Default")
      (node (ref "J5") (pin "39") (pinfunction "39_39") (pintype "passive"))
    )
    (net (code "138") (name "unconnected-(J5-Pad40)") (class "Default")
      (node (ref "J5") (pin "40") (pinfunction "40_40") (pintype "passive"))
    )
    (net (code "139") (name "unconnected-(K1-PTA0-Pad30)") (class "Default")
      (node (ref "K1") (pin "30") (pinfunction "PTA0_30") (pintype "bidirectional"))
    )
    (net (code "140") (name "unconnected-(K1-PTA1-Pad31)") (class "Default")
      (node (ref "K1") (pin "31") (pinfunction "PTA1_31") (pintype "bidirectional"))
    )
    (net (code "141") (name "unconnected-(K1-PTA2-Pad32)") (class "Default")
      (node (ref "K1") (pin "32") (pinfunction "PTA2_32") (pintype "bidirectional"))
    )
    (net (code "142") (name "unconnected-(K1-PTA3-Pad7)") (class "Default")
      (node (ref "K1") (pin "7") (pinfunction "PTA3_7") (pintype "bidirectional"))
    )
    (net (code "143") (name "unconnected-(K1-PTA5-Pad9)") (class "Default")
      (node (ref "K1") (pin "9") (pinfunction "PTA5_9") (pintype "bidirectional"))
    )
    (net (code "144") (name "unconnected-(K1-PTB3-Pad23)") (class "Default")
      (node (ref "K1") (pin "23") (pinfunction "PTB3_23") (pintype "bidirectional"))
    )
    (net (code "145") (name "unconnected-(K1-PTB4-Pad24)") (class "Default")
      (node (ref "K1") (pin "24") (pinfunction "PTB4_24") (pintype "bidirectional"))
    )
    (net (code "146") (name "unconnected-(K2-EXTAL32-Pad20)") (class "Default")
      (node (ref "K2") (pin "20") (pinfunction "EXTAL32_20") (pintype "bidirectional"))
    )
    (net (code "147") (name "unconnected-(K2-VREGIN-Pad8)") (class "Default")
      (node (ref "K2") (pin "8") (pinfunction "VREGIN_8") (pintype "bidirectional"))
    )
    (net (code "148") (name "unconnected-(K2-XTAL32-Pad19)") (class "Default")
      (node (ref "K2") (pin "19") (pinfunction "XTAL32_19") (pintype "bidirectional"))
    )
    (net (code "149") (name "unconnected-(U1-NC-Pad1)") (class "Default")
      (node (ref "U1") (pin "1") (pinfunction "NC_1") (pintype "bidirectional"))
    )
    (net (code "150") (name "unconnected-(U1-PadCD1)") (class "Default")
      (node (ref "U1") (pin "CD1") (pinfunction "CD1_CD1") (pintype "bidirectional"))
    )
    (net (code "151") (name "unconnected-(U1-RSV-Pad8)") (class "Default")
      (node (ref "U1") (pin "8") (pinfunction "RSV_8") (pintype "bidirectional"))
    )
    (net (code "152") (name "unconnected-(U2-CPFLT-Pad18)") (class "Default")
      (node (ref "U2") (pin "18") (pinfunction "CPFLT_18") (pintype "passive"))
    )
    (net (code "153") (name "unconnected-(U2-NC-Pad28)") (class "Default")
      (node (ref "U2") (pin "28") (pinfunction "NC_28") (pintype "passive"))
    )
    (net (code "154") (name "unconnected-(U2-NC_2-Pad8)") (class "Default")
      (node (ref "U2") (pin "8") (pinfunction "NC_2_8") (pintype "passive"))
    )
    (net (code "155") (name "unconnected-(U2-NC_3-Pad9)") (class "Default")
      (node (ref "U2") (pin "9") (pinfunction "NC_3_9") (pintype "passive"))
    )
    (net (code "156") (name "unconnected-(U2-NC_4-Pad17)") (class "Default")
      (node (ref "U2") (pin "17") (pinfunction "NC_4_17") (pintype "passive"))
    )
    (net (code "157") (name "unconnected-(U2-NC_5-Pad19)") (class "Default")
      (node (ref "U2") (pin "19") (pinfunction "NC_5_19") (pintype "passive"))
    )
    (net (code "158") (name "unconnected-(U2-NC_6-Pad22)") (class "Default")
      (node (ref "U2") (pin "22") (pinfunction "NC_6_22") (pintype "passive"))
    )
    (net (code "159") (name "unconnected-(U5-AIO1-Pad35)") (class "Default")
      (node (ref "U5") (pin "35") (pinfunction "AIO1_35") (pintype "bidirectional"))
    )
    (net (code "160") (name "unconnected-(U5-AIO2-Pad30)") (class "Default")
      (node (ref "U5") (pin "30") (pinfunction "AIO2_30") (pintype "bidirectional"))
    )
    (net (code "161") (name "unconnected-(U5-NC-Pad26)") (class "Default")
      (node (ref "U5") (pin "26") (pinfunction "NC_26") (pintype "bidirectional"))
    )
    (net (code "162") (name "unconnected-(U5-PCMCLK-Pad7)") (class "Default")
      (node (ref "U5") (pin "7") (pinfunction "PCMCLK_7") (pintype "bidirectional"))
    )
    (net (code "163") (name "unconnected-(U5-PCMIN-Pad9)") (class "Default")
      (node (ref "U5") (pin "9") (pinfunction "PCMIN_9") (pintype "bidirectional"))
    )
    (net (code "164") (name "unconnected-(U5-PCMOUT-Pad10)") (class "Default")
      (node (ref "U5") (pin "10") (pinfunction "PCMOUT_10") (pintype "bidirectional"))
    )
    (net (code "165") (name "unconnected-(U5-PCMSYNC-Pad8)") (class "Default")
      (node (ref "U5") (pin "8") (pinfunction "PCMSYNC_8") (pintype "bidirectional"))
    )
    (net (code "166") (name "unconnected-(U5-PIO3-Pad20)") (class "Default")
      (node (ref "U5") (pin "20") (pinfunction "PIO3_20") (pintype "bidirectional"))
    )
    (net (code "167") (name "unconnected-(U5-PIO6-Pad3)") (class "Default")
      (node (ref "U5") (pin "3") (pinfunction "PIO6_3") (pintype "bidirectional"))
    )
    (net (code "168") (name "unconnected-(U5-PIO7-Pad4)") (class "Default")
      (node (ref "U5") (pin "4") (pinfunction "PIO7_4") (pintype "bidirectional"))
    )
    (net (code "169") (name "unconnected-(U5-PIO8-Pad34)") (class "Default")
      (node (ref "U5") (pin "34") (pinfunction "PIO8_34") (pintype "bidirectional"))
    )
    (net (code "170") (name "unconnected-(U5-PIO9-Pad33)") (class "Default")
      (node (ref "U5") (pin "33") (pinfunction "PIO9_33") (pintype "bidirectional"))
    )
    (net (code "171") (name "unconnected-(U5-PIO10-Pad32)") (class "Default")
      (node (ref "U5") (pin "32") (pinfunction "PIO10_32") (pintype "bidirectional"))
    )
    (net (code "172") (name "unconnected-(U5-PIO11-Pad31)") (class "Default")
      (node (ref "U5") (pin "31") (pinfunction "PIO11_31") (pintype "bidirectional"))
    )
    (net (code "173") (name "unconnected-(U5-RESET-Pad5)") (class "Default")
      (node (ref "U5") (pin "5") (pinfunction "RESET_5") (pintype "bidirectional"))
    )
    (net (code "174") (name "unconnected-(U5-SPICLK-Pad6)") (class "Default")
      (node (ref "U5") (pin "6") (pinfunction "SPICLK_6") (pintype "bidirectional"))
    )
    (net (code "175") (name "unconnected-(U5-SPICSB-Pad23)") (class "Default")
      (node (ref "U5") (pin "23") (pinfunction "SPICSB_23") (pintype "bidirectional"))
    )
    (net (code "176") (name "unconnected-(U5-SPIMISO-Pad24)") (class "Default")
      (node (ref "U5") (pin "24") (pinfunction "SPIMISO_24") (pintype "bidirectional"))
    )
    (net (code "177") (name "unconnected-(U5-SPIMOSI-Pad2)") (class "Default")
      (node (ref "U5") (pin "2") (pinfunction "SPIMOSI_2") (pintype "bidirectional"))
    )
    (net (code "178") (name "unconnected-(U5-USBD+-Pad17)") (class "Default")
      (node (ref "U5") (pin "17") (pinfunction "USBD+_17") (pintype "bidirectional"))
    )
    (net (code "179") (name "unconnected-(U5-USBD--Pad18)") (class "Default")
      (node (ref "U5") (pin "18") (pinfunction "USBD-_18") (pintype "bidirectional"))
    )
  )
)
